# VoltageRegulatorShield.net
KiCad netlist of a schematic drawn in EAGLE
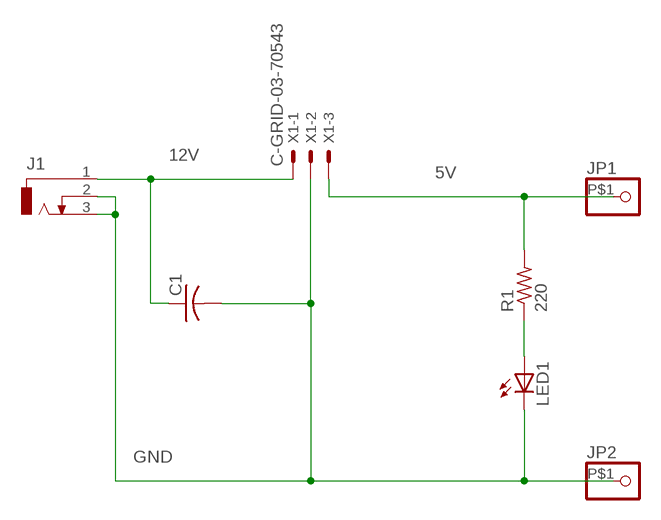
[diagram p0: schematic, sheet 1]

(export (version "E")
  (design (tool "Eeschema 10.0.6"))
  (components
    (comp (ref "C1")
      (value "C-US025-025X050")
      (footprint "eagle-import:C025-025X050")
      (libsource (lib "eagle-import") (part "C-US025-025X050"))
    )
    (comp (ref "J1")
      (value "DCJ0303")
      (footprint "eagle-import:DCJ0303")
      (libsource (lib "eagle-import") (part "DCJ0303"))
    )
    (comp (ref "JP1")
      (value "PINHD-1X1-BIGPOGO")
      (footprint "eagle-import:1X1-BIGPOGO")
      (libsource (lib "eagle-import") (part "PINHD-1X1-BIGPOGO"))
    )
    (comp (ref "JP2")
      (value "PINHD-1X1-BIGPOGO")
      (footprint "eagle-import:1X1-BIGPOGO")
      (libsource (lib "eagle-import") (part "PINHD-1X1-BIGPOGO"))
    )
    (comp (ref "LED1")
      (value "LED5MM")
      (footprint "eagle-import:LED5MM")
      (libsource (lib "eagle-import") (part "LED5MM"))
    )
    (comp (ref "R1")
      (value "220")
      (footprint "eagle-import:V234_12")
      (libsource (lib "eagle-import") (part "R-US_V234/12"))
    )
    (comp (ref "X1")
      (value "C-GRID-03-70543")
      (footprint "eagle-import:70543-03")
      (fields (field (name "MF") "MOLEX"))
      (libsource (lib "eagle-import") (part "C-GRID-03-70543"))
    )
  )
  (nets
    (net (code "1") (name "/5V") (class "Default")
      (node (ref "JP1") (pin "P$1") (pinfunction "1_P$1") (pintype "passive"))
      (node (ref "R1") (pin "2") (pinfunction "2_2") (pintype "passive"))
      (node (ref "X1") (pin "3") (pinfunction "S_3") (pintype "passive"))
    )
    (net (code "2") (name "/12V") (class "Default")
      (node (ref "C1") (pin "1") (pinfunction "1_1") (pintype "passive"))
      (node (ref "J1") (pin "1") (pinfunction "1_1") (pintype "passive"))
      (node (ref "X1") (pin "1") (pinfunction "S_1") (pintype "passive"))
    )
    (net (code "3") (name "/GND") (class "Default")
      (node (ref "C1") (pin "2") (pinfunction "2_2") (pintype "passive"))
      (node (ref "J1") (pin "2") (pinfunction "2_2") (pintype "passive"))
      (node (ref "J1") (pin "3") (pinfunction "3_3") (pintype "passive"))
      (node (ref "JP2") (pin "P$1") (pinfunction "1_P$1") (pintype "passive"))
      (node (ref "LED1") (pin "K") (pinfunction "C_K") (pintype "passive"))
      (node (ref "X1") (pin "2") (pinfunction "S_2") (pintype "passive"))
    )
    (net (code "4") (name "Net-(LED1-PadA)") (class "Default")
      (node (ref "LED1") (pin "A") (pinfunction "A_A") (pintype "passive"))
      (node (ref "R1") (pin "1") (pinfunction "1_1") (pintype "passive"))
    )
  )
)
